# MAZ000175_-_Diagrama_el_ctrico.net
KiCad netlist of a schematic drawn in Altium Designer
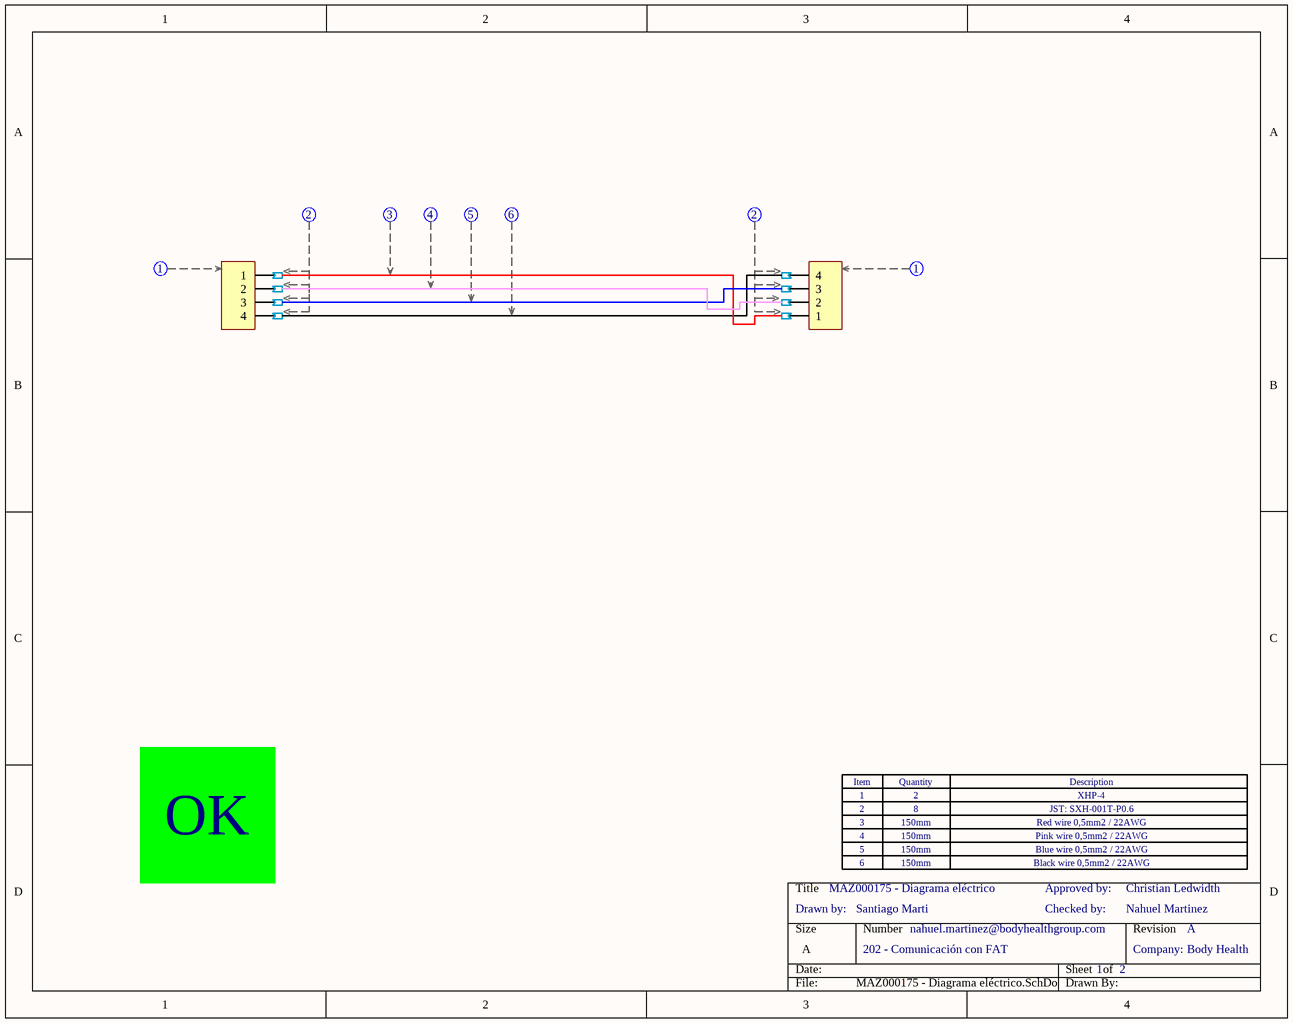
[diagram p0: MAZ000175 - Diagrama eléctrico.SchDoc]

(export (version "E")
  (design (tool "Eeschema 10.0.6"))
  (components
    (comp (ref "Con1")
      (value "XHP-4")
      (description "CONN HOUSING 2.5MM 4POS")
      (libsource (lib "LibreriaParaPlanos") (part "XHP-4"))
    )
    (comp (ref "Con2")
      (value "XHP-4")
      (description "CONN HOUSING 2.5MM 4POS")
      (libsource (lib "LibreriaParaPlanos") (part "XHP-4"))
    )
    (comp (ref "Soc1")
      (value "sock_XHP_SXH-002T-P0.6")
      (description "CONN SOCKET 26-30AWG CRIMP TIN")
      (libsource (lib "LibreriaParaPlanos") (part "sock_XHP_SXH-002T-P0.6"))
    )
    (comp (ref "Soc2")
      (value "sock_XHP_SXH-002T-P0.6")
      (description "CONN SOCKET 26-30AWG CRIMP TIN")
      (libsource (lib "LibreriaParaPlanos") (part "sock_XHP_SXH-002T-P0.6"))
    )
    (comp (ref "Soc3")
      (value "sock_XHP_SXH-002T-P0.6")
      (description "CONN SOCKET 26-30AWG CRIMP TIN")
      (libsource (lib "LibreriaParaPlanos") (part "sock_XHP_SXH-002T-P0.6"))
    )
    (comp (ref "Soc4")
      (value "sock_XHP_SXH-002T-P0.6")
      (description "CONN SOCKET 26-30AWG CRIMP TIN")
      (libsource (lib "LibreriaParaPlanos") (part "sock_XHP_SXH-002T-P0.6"))
    )
    (comp (ref "Soc5")
      (value "sock_XHP_SXH-002T-P0.6")
      (description "CONN SOCKET 26-30AWG CRIMP TIN")
      (libsource (lib "LibreriaParaPlanos") (part "sock_XHP_SXH-002T-P0.6"))
    )
    (comp (ref "Soc6")
      (value "sock_XHP_SXH-002T-P0.6")
      (description "CONN SOCKET 26-30AWG CRIMP TIN")
      (libsource (lib "LibreriaParaPlanos") (part "sock_XHP_SXH-002T-P0.6"))
    )
    (comp (ref "Soc7")
      (value "sock_XHP_SXH-002T-P0.6")
      (description "CONN SOCKET 26-30AWG CRIMP TIN")
      (libsource (lib "LibreriaParaPlanos") (part "sock_XHP_SXH-002T-P0.6"))
    )
    (comp (ref "Soc8")
      (value "sock_XHP_SXH-002T-P0.6")
      (description "CONN SOCKET 26-30AWG CRIMP TIN")
      (libsource (lib "LibreriaParaPlanos") (part "sock_XHP_SXH-002T-P0.6"))
    )
    (comp (ref "Zoc1")
      (value "Zócalo_Header")
      (description "Header para el zócalo de referencias")
      (libsource (lib "LibreriaParaPlanos") (part "Zócalo_Header"))
    )
    (comp (ref "Zoc2")
      (value "Zócalo_Item")
      (description "Ítem para el zócalo de referencias")
      (libsource (lib "LibreriaParaPlanos") (part "Zócalo_Item"))
    )
    (comp (ref "Zoc3")
      (value "Zócalo_Item")
      (description "Ítem para el zócalo de referencias")
      (libsource (lib "LibreriaParaPlanos") (part "Zócalo_Item"))
    )
    (comp (ref "Zoc4")
      (value "Zócalo_Item")
      (description "Ítem para el zócalo de referencias")
      (libsource (lib "LibreriaParaPlanos") (part "Zócalo_Item"))
    )
    (comp (ref "Zoc5")
      (value "Zócalo_Item")
      (description "Ítem para el zócalo de referencias")
      (libsource (lib "LibreriaParaPlanos") (part "Zócalo_Item"))
    )
    (comp (ref "Zoc6")
      (value "Zócalo_Item")
      (description "Ítem para el zócalo de referencias")
      (libsource (lib "LibreriaParaPlanos") (part "Zócalo_Item"))
    )
    (comp (ref "Zoc7")
      (value "Zócalo_Item")
      (description "Ítem para el zócalo de referencias")
      (libsource (lib "LibreriaParaPlanos") (part "Zócalo_Item"))
    )
  )
  (nets
    (net (code "1") (name "Net-(Con1-Pad1)") (class "Default")
      (node (ref "Con1") (pin "1") (pinfunction "1_1") (pintype "passive"))
      (node (ref "Soc1") (pin "0") (pinfunction "0_0") (pintype "passive"))
    )
    (net (code "2") (name "Net-(Con1-Pad2)") (class "Default")
      (node (ref "Con1") (pin "2") (pinfunction "2_2") (pintype "passive"))
      (node (ref "Soc3") (pin "0") (pinfunction "0_0") (pintype "passive"))
    )
    (net (code "3") (name "Net-(Con1-Pad3)") (class "Default")
      (node (ref "Con1") (pin "3") (pinfunction "3_3") (pintype "passive"))
      (node (ref "Soc5") (pin "0") (pinfunction "0_0") (pintype "passive"))
    )
    (net (code "4") (name "Net-(Con1-Pad4)") (class "Default")
      (node (ref "Con1") (pin "4") (pinfunction "4_4") (pintype "passive"))
      (node (ref "Soc7") (pin "0") (pinfunction "0_0") (pintype "passive"))
    )
    (net (code "5") (name "Net-(Con2-Pad1)") (class "Default")
      (node (ref "Con2") (pin "1") (pinfunction "1_1") (pintype "passive"))
      (node (ref "Soc8") (pin "0") (pinfunction "0_0") (pintype "passive"))
    )
    (net (code "6") (name "Net-(Con2-Pad2)") (class "Default")
      (node (ref "Con2") (pin "2") (pinfunction "2_2") (pintype "passive"))
      (node (ref "Soc6") (pin "0") (pinfunction "0_0") (pintype "passive"))
    )
    (net (code "7") (name "Net-(Con2-Pad3)") (class "Default")
      (node (ref "Con2") (pin "3") (pinfunction "3_3") (pintype "passive"))
      (node (ref "Soc4") (pin "0") (pinfunction "0_0") (pintype "passive"))
    )
    (net (code "8") (name "Net-(Con2-Pad4)") (class "Default")
      (node (ref "Con2") (pin "4") (pinfunction "4_4") (pintype "passive"))
      (node (ref "Soc2") (pin "0") (pinfunction "0_0") (pintype "passive"))
    )
    (net (code "9") (name "Net-(Soc1-Pad1)") (class "Default")
      (node (ref "Soc1") (pin "1") (pinfunction "1_1") (pintype "passive"))
      (node (ref "Soc8") (pin "1") (pinfunction "1_1") (pintype "passive"))
    )
    (net (code "10") (name "Net-(Soc2-Pad1)") (class "Default")
      (node (ref "Soc2") (pin "1") (pinfunction "1_1") (pintype "passive"))
      (node (ref "Soc7") (pin "1") (pinfunction "1_1") (pintype "passive"))
    )
    (net (code "11") (name "Net-(Soc3-Pad1)") (class "Default")
      (node (ref "Soc3") (pin "1") (pinfunction "1_1") (pintype "passive"))
      (node (ref "Soc6") (pin "1") (pinfunction "1_1") (pintype "passive"))
    )
    (net (code "12") (name "Net-(Soc4-Pad1)") (class "Default")
      (node (ref "Soc4") (pin "1") (pinfunction "1_1") (pintype "passive"))
      (node (ref "Soc5") (pin "1") (pinfunction "1_1") (pintype "passive"))
    )
  )
)
